# Power.net
KiCad netlist of a schematic drawn in Altium Designer
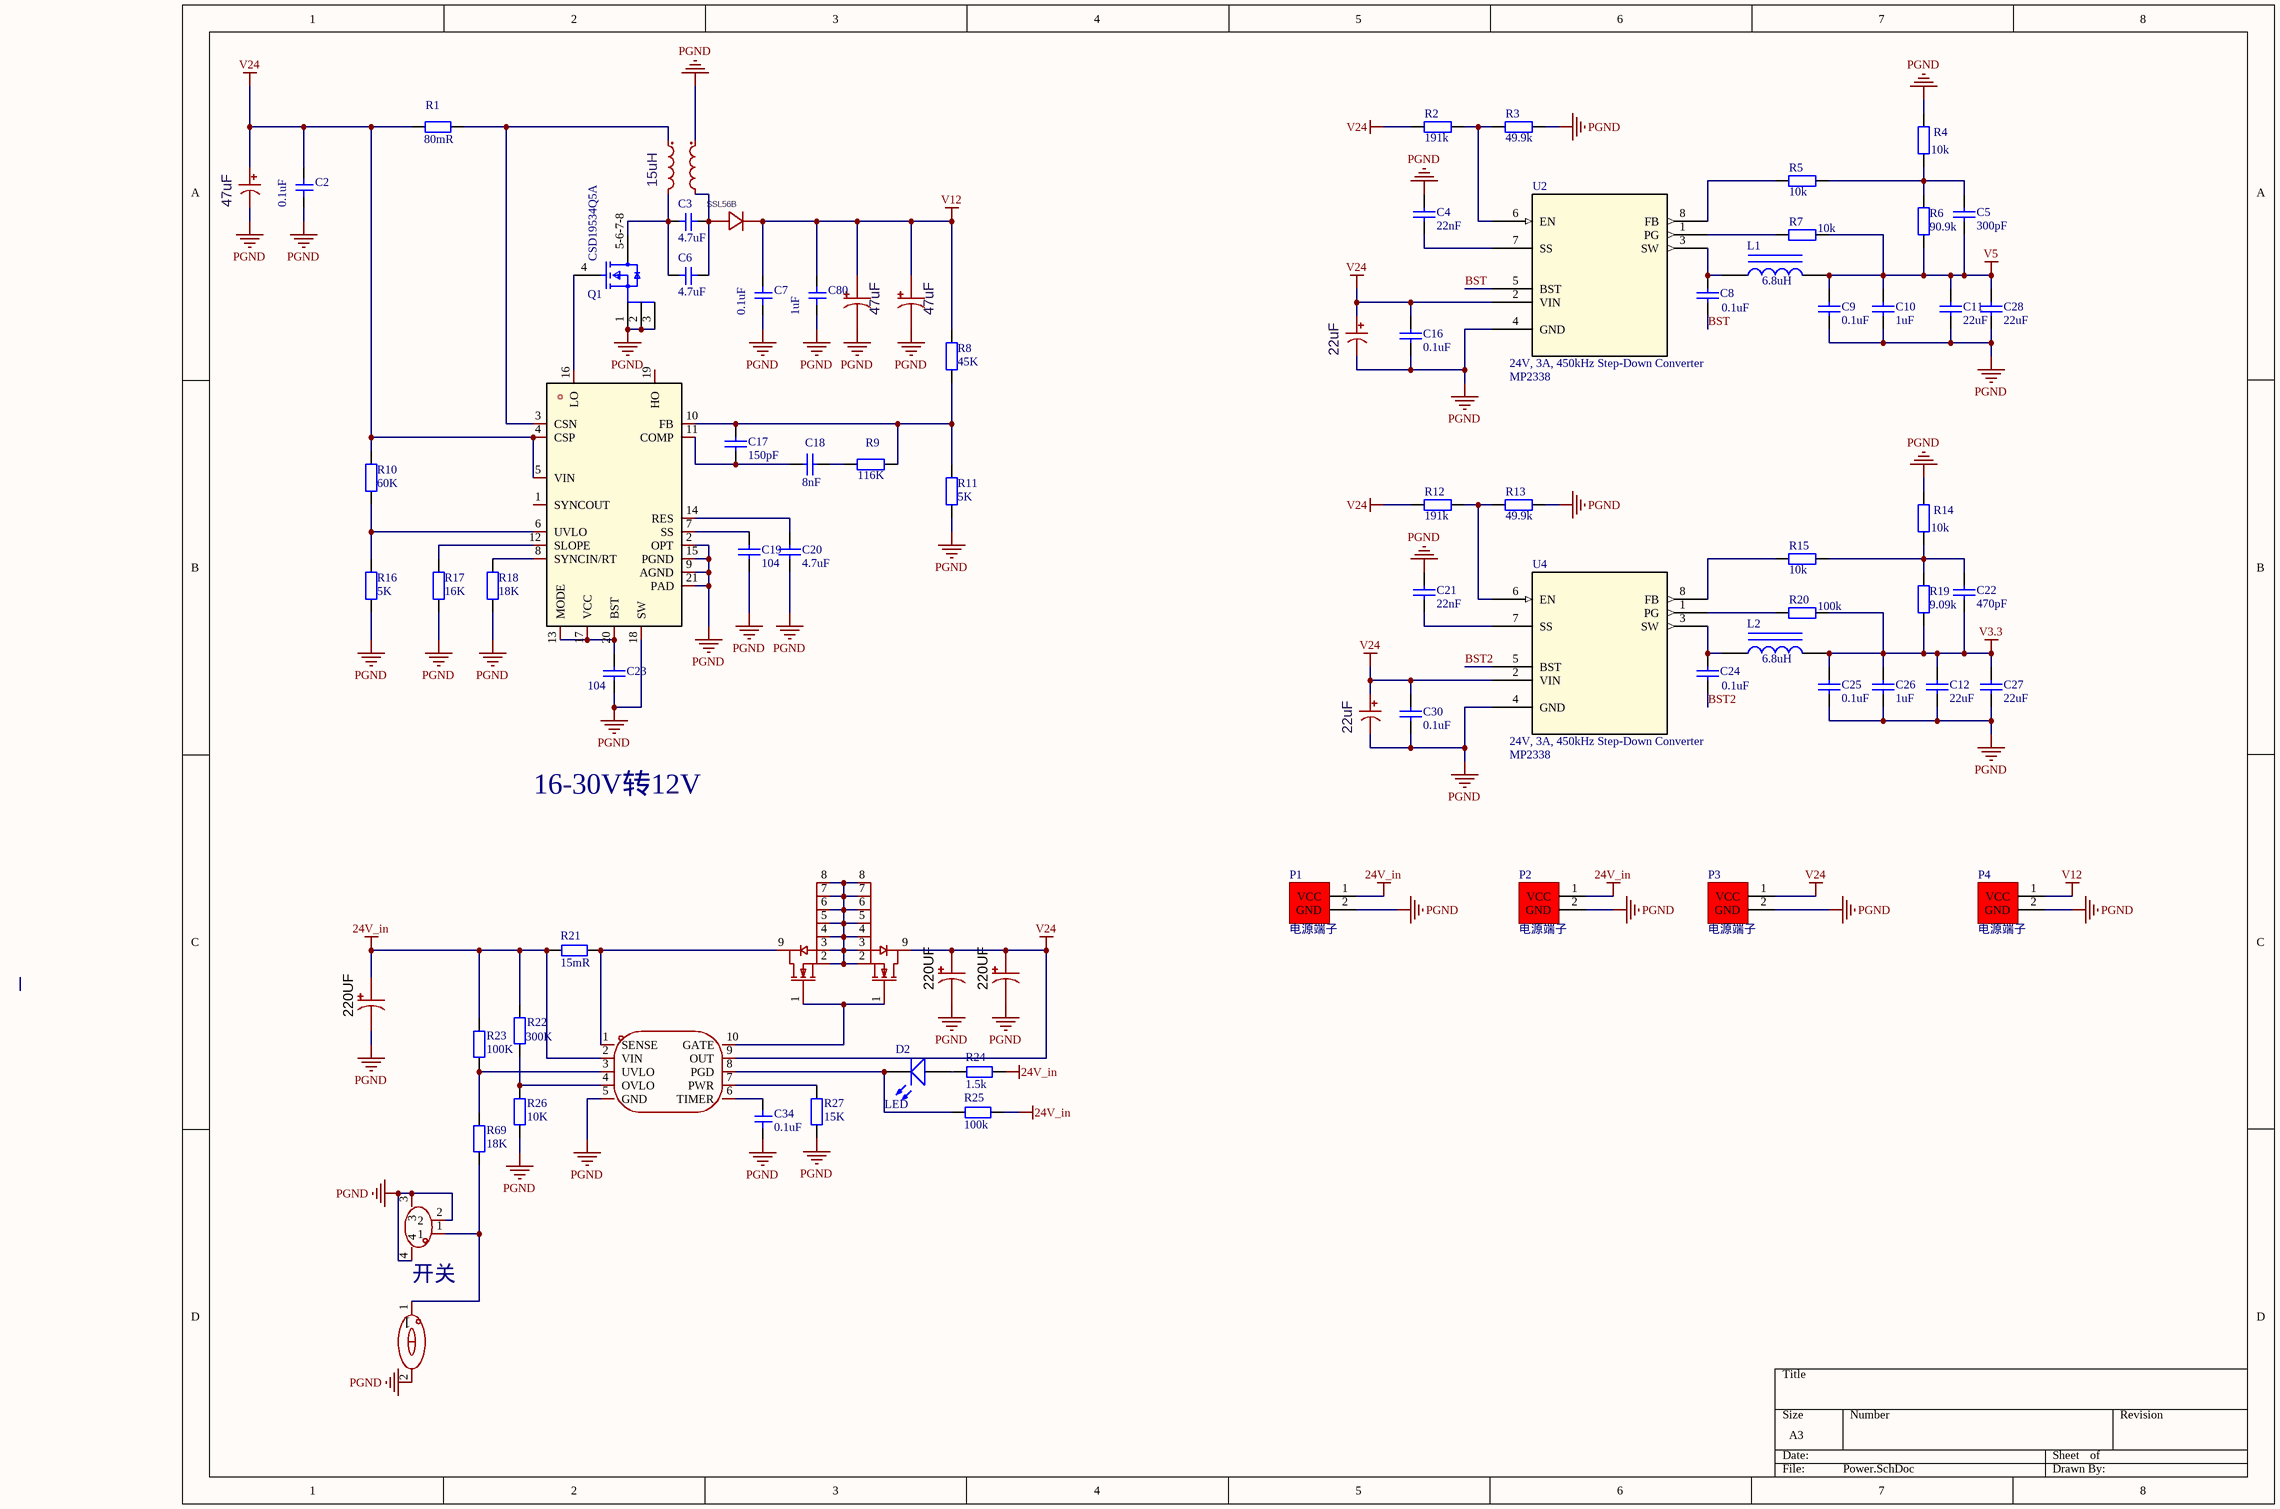
[diagram p0: Power.SchDoc]

(export (version "E")
  (design (tool "Eeschema 10.0.6"))
  (components
    (comp (ref "C1")
      (value "47uF")
      (footprint "CAP-SMD_BD6.3-L6.6-W6.6-LS7.6-FD")
      (description "电解电容")
      (fields (field (name "MANUFACTURER") "ROQANG(容强)") (field (name "MANUFACTURER PART") "RVT1H470M0607"))
      (libsource (lib "PBK11") (part "cap"))
    )
    (comp (ref "C2")
      (value "0.1uF")
      (footprint "0603C")
      (description "无极贴片电容")
      (libsource (lib "PBK11") (part "Cap1"))
    )
    (comp (ref "C3")
      (value "4.7uF")
      (footprint "1206_C")
      (description "无极贴片电容")
      (libsource (lib "PBK11") (part "Cap1"))
    )
    (comp (ref "C4")
      (value "22nF")
      (footprint "0402_C")
      (description "贴片电容")
      (libsource (lib "SFerret") (part "SMT_Cap"))
    )
    (comp (ref "C5")
      (value "300pF")
      (footprint "0402_C")
      (description "贴片电容")
      (libsource (lib "SFerret") (part "SMT_Cap"))
    )
    (comp (ref "C6")
      (value "4.7uF")
      (footprint "1206_C")
      (description "无极贴片电容")
      (libsource (lib "PBK11") (part "Cap1"))
    )
    (comp (ref "C7")
      (value "0.1uF")
      (footprint "0603C")
      (description "无极贴片电容")
      (libsource (lib "PBK11") (part "Cap1"))
    )
    (comp (ref "C8")
      (value "0.1uF")
      (footprint "0603_C")
      (description "贴片电容")
      (libsource (lib "SFerret") (part "SMT_Cap"))
    )
    (comp (ref "C9")
      (value "0.1uF")
      (footprint "0603_C")
      (description "贴片电容")
      (libsource (lib "SFerret") (part "SMT_Cap"))
    )
    (comp (ref "C10")
      (value "1uF")
      (footprint "0603_C")
      (description "贴片电容")
      (libsource (lib "SFerret") (part "SMT_Cap"))
    )
    (comp (ref "C11")
      (value "22uF")
      (footprint "1210_C")
      (description "贴片电容")
      (libsource (lib "SFerret") (part "SMT_Cap"))
    )
    (comp (ref "C12")
      (value "22uF")
      (footprint "1210_C")
      (description "贴片电容")
      (libsource (lib "SFerret") (part "SMT_Cap"))
    )
    (comp (ref "C13")
      (value "47uF")
      (footprint "CAP-SMD_BD6.3-L6.6-W6.6-LS7.6-FD")
      (description "47uf 63v 2.1A@100KHZ")
      (fields (field (name "MANUFACTURER") "PANASONIC(松下)") (field (name "MANUFACTURER PART") "50SVPF39M"))
      (libsource (lib "PBK11") (part "cap2"))
    )
    (comp (ref "C14")
      (value "47uF")
      (footprint "CAP-SMD_BD6.3-L6.6-W6.6-LS7.6-FD")
      (description "47uf 63v 2.1A@100KHZ")
      (fields (field (name "MANUFACTURER") "PANASONIC(松下)") (field (name "MANUFACTURER PART") "50SVPF39M"))
      (libsource (lib "PBK11") (part "cap2"))
    )
    (comp (ref "C15")
      (value "22uF")
      (footprint "CAP-SMD_BD6.3-L6.6-W6.6-LS7.6-FD")
      (description "电解电容")
      (fields (field (name "MANUFACTURER") "ROQANG(容强)") (field (name "MANUFACTURER PART") "RVT1H470M0607"))
      (libsource (lib "PBK11") (part "cap"))
    )
    (comp (ref "C16")
      (value "0.1uF")
      (footprint "0603_C")
      (description "贴片电容")
      (libsource (lib "SFerret") (part "SMT_Cap"))
    )
    (comp (ref "C17")
      (value "150pF")
      (footprint "0402_C")
      (description "贴片电容")
      (libsource (lib "PBK11") (part "SMT_Cap"))
    )
    (comp (ref "C18")
      (value "8nF")
      (footprint "0402_C")
      (description "贴片电容")
      (libsource (lib "PBK11") (part "SMT_Cap"))
    )
    (comp (ref "C19")
      (value "104")
      (footprint "0402_C")
      (description "贴片电容")
      (libsource (lib "PBK11") (part "SMT_Cap"))
    )
    (comp (ref "C20")
      (value "4.7uF")
      (footprint "0603_C")
      (description "贴片电容")
      (libsource (lib "PBK11") (part "SMT_Cap"))
    )
    (comp (ref "C21")
      (value "22nF")
      (footprint "0402_C")
      (description "贴片电容")
      (libsource (lib "SFerret") (part "SMT_Cap"))
    )
    (comp (ref "C22")
      (value "470pF")
      (footprint "0402_C")
      (description "贴片电容")
      (libsource (lib "SFerret") (part "SMT_Cap"))
    )
    (comp (ref "C23")
      (value "104")
      (footprint "0402_C")
      (description "贴片电容")
      (libsource (lib "PBK11") (part "SMT_Cap"))
    )
    (comp (ref "C24")
      (value "0.1uF")
      (footprint "0603_C")
      (description "贴片电容")
      (libsource (lib "SFerret") (part "SMT_Cap"))
    )
    (comp (ref "C25")
      (value "0.1uF")
      (footprint "0603_C")
      (description "贴片电容")
      (libsource (lib "SFerret") (part "SMT_Cap"))
    )
    (comp (ref "C26")
      (value "1uF")
      (footprint "0603_C")
      (description "贴片电容")
      (libsource (lib "SFerret") (part "SMT_Cap"))
    )
    (comp (ref "C27")
      (value "22uF")
      (footprint "1210_C")
      (description "贴片电容")
      (libsource (lib "SFerret") (part "SMT_Cap"))
    )
    (comp (ref "C28")
      (value "22uF")
      (footprint "1210_C")
      (description "贴片电容")
      (libsource (lib "SFerret") (part "SMT_Cap"))
    )
    (comp (ref "C29")
      (value "22uF")
      (footprint "CAP-SMD_BD6.3-L6.6-W6.6-LS7.6-FD")
      (description "电解电容")
      (fields (field (name "MANUFACTURER") "ROQANG(容强)") (field (name "MANUFACTURER PART") "RVT1H470M0607"))
      (libsource (lib "PBK11") (part "cap"))
    )
    (comp (ref "C30")
      (value "0.1uF")
      (footprint "0603_C")
      (description "贴片电容")
      (libsource (lib "SFerret") (part "SMT_Cap"))
    )
    (comp (ref "C31")
      (value "220UF")
      (footprint "CAP-SMD_BD10.0-L10.3-W10.3-LS11.3-FD")
      (description "4.7uf 50v 14mA@120HZ")
      (fields (field (name "MANUFACTURER") "ROQANG(容强)") (field (name "MANUFACTURER PART") "VT1H4R7M0405"))
      (libsource (lib "") (part "cap_1"))
    )
    (comp (ref "C32")
      (value "220UF")
      (footprint "CAP-SMD_BD10.0-L10.3-W10.3-LS11.3-FD")
      (description "4.7uf 50v 14mA@120HZ")
      (fields (field (name "MANUFACTURER") "ROQANG(容强)") (field (name "MANUFACTURER PART") "VT1H4R7M0405"))
      (libsource (lib "") (part "cap_1"))
    )
    (comp (ref "C33")
      (value "220UF")
      (footprint "CAP-SMD_BD10.0-L10.3-W10.3-LS11.3-FD")
      (description "4.7uf 50v 14mA@120HZ")
      (fields (field (name "MANUFACTURER") "ROQANG(容强)") (field (name "MANUFACTURER PART") "VT1H4R7M0405"))
      (libsource (lib "") (part "cap_1"))
    )
    (comp (ref "C34")
      (value "0.1uF")
      (footprint "0402_C")
      (description "无极贴片电容")
      (libsource (lib "PBK11") (part "Cap1"))
    )
    (comp (ref "C80")
      (value "1uF")
      (footprint "0603C")
      (description "无极贴片电容")
      (libsource (lib "PBK11") (part "Cap1"))
    )
    (comp (ref "D1")
      (value "SSL56B")
      (footprint "SMBF_L4.3-W3.6-LS5.3-RD")
      (description "正向压降(Vf): 500mV@5A\r\n直流反向耐压(Vr): 60V\r\n整流电流: 5A 肖特基二极管")
      (fields (field (name "MANUFACTURER") "宏迦橙"))
      (libsource (lib "PBK11") (part "SSL56B_C28646279"))
    )
    (comp (ref "D2")
      (value "LED")
      (footprint "0805_LED")
      (description "发光二极管")
      (libsource (lib "PBK11") (part "LED"))
    )
    (comp (ref "L1")
      (value "6.8uH")
      (footprint "IND-SMD_L7.0-W6.6")
      (description "功率电感")
      (libsource (lib "SFerret") (part "SMT_Iud_Power"))
    )
    (comp (ref "L2")
      (value "6.8uH")
      (footprint "IND-SMD_L7.0-W6.6")
      (description "功率电感")
      (libsource (lib "SFerret") (part "SMT_Iud_Power"))
    )
    (comp (ref "P1") (value "电源端子") (footprint "XT60PB-F") (libsource (lib "PBK11") (part "电源端子")))
    (comp (ref "P2") (value "电源端子") (footprint "XT60PB-F") (libsource (lib "PBK11") (part "电源端子")))
    (comp (ref "P3") (value "电源端子") (footprint "XT60PB-F") (libsource (lib "PBK11") (part "电源端子")))
    (comp (ref "P4") (value "电源端子") (footprint "XT30-F") (libsource (lib "PBK11") (part "电源端子")))
    (comp (ref "Q1")
      (value "CSD19534Q5A")
      (footprint "FP-DQJ0008A-MFG")
      (description "MOSFET N-CH 100V 50 8SON")
      (fields
        (field (name "OCTOPART") "https://octopart.com/csd19534q5a-texas+instruments-46749514")
        (field (name "MANUFACTURER") "Texas Instruments")
      )
      (libsource (lib "PBK11") (part "CMP-04962-000018-1"))
    )
    (comp (ref "Q2")
      (value "HYG006N04LS1TA")
      (footprint "TOLL-8_L10.4-W9.9-P1.20-LS11.7-BL")
      (fields (field (name "MANUFACTURER") "HUAYI(华羿微)"))
      (libsource (lib "PBK11") (part "HYG006N04LS1TA"))
    )
    (comp (ref "Q3")
      (value "HYG006N04LS1TA")
      (footprint "TOLL-8_L10.4-W9.9-P1.20-LS11.7-BL")
      (fields (field (name "MANUFACTURER") "HUAYI(华羿微)"))
      (libsource (lib "PBK11") (part "HYG006N04LS1TA"))
    )
    (comp (ref "R1")
      (value "80mR")
      (footprint "2512")
      (description "电阻")
      (libsource (lib "PBK11") (part "Res"))
    )
    (comp (ref "R2")
      (value "191k")
      (footprint "0402_R")
      (description "贴片电阻")
      (libsource (lib "SFerret") (part "SMT_Res"))
    )
    (comp (ref "R3")
      (value "49.9k")
      (footprint "0402_R")
      (description "贴片电阻")
      (libsource (lib "SFerret") (part "SMT_Res"))
    )
    (comp (ref "R4")
      (value "10k")
      (footprint "0402_R")
      (description "贴片电阻")
      (libsource (lib "") (part "SMT_Res_1"))
    )
    (comp (ref "R5")
      (value "10k")
      (footprint "0402_R")
      (description "贴片电阻")
      (libsource (lib "SFerret") (part "SMT_Res"))
    )
    (comp (ref "R6")
      (value "90.9k")
      (footprint "0402_R")
      (description "贴片电阻")
      (libsource (lib "") (part "SMT_Res_1"))
    )
    (comp (ref "R7")
      (value "10k")
      (footprint "0402_R")
      (description "贴片电阻")
      (libsource (lib "") (part "SMT_Res_2"))
    )
    (comp (ref "R8")
      (value "45K")
      (footprint "0402_R")
      (description "贴片电阻")
      (libsource (lib "") (part "SMT_Res_1"))
    )
    (comp (ref "R9")
      (value "116K")
      (footprint "0402_R")
      (description "贴片电阻")
      (libsource (lib "PBK11") (part "SMT_Res"))
    )
    (comp (ref "R10")
      (value "60K")
      (footprint "0402_R")
      (description "贴片电阻")
      (libsource (lib "PBK11") (part "SMT_Res_1"))
    )
    (comp (ref "R11")
      (value "5K")
      (footprint "0402_R")
      (description "贴片电阻")
      (libsource (lib "") (part "SMT_Res_1"))
    )
    (comp (ref "R12")
      (value "191k")
      (footprint "0402_R")
      (description "贴片电阻")
      (libsource (lib "SFerret") (part "SMT_Res"))
    )
    (comp (ref "R13")
      (value "49.9k")
      (footprint "0402_R")
      (description "贴片电阻")
      (libsource (lib "SFerret") (part "SMT_Res"))
    )
    (comp (ref "R14")
      (value "10k")
      (footprint "0402_R")
      (description "贴片电阻")
      (libsource (lib "") (part "SMT_Res_1"))
    )
    (comp (ref "R15")
      (value "10k")
      (footprint "0402_R")
      (description "贴片电阻")
      (libsource (lib "SFerret") (part "SMT_Res"))
    )
    (comp (ref "R16")
      (value "5K")
      (footprint "0402_R")
      (description "贴片电阻")
      (libsource (lib "PBK11") (part "SMT_Res_1"))
    )
    (comp (ref "R17")
      (value "16K")
      (footprint "0402_R")
      (description "贴片电阻")
      (libsource (lib "PBK11") (part "SMT_Res_1"))
    )
    (comp (ref "R18")
      (value "18K")
      (footprint "0402_R")
      (description "贴片电阻")
      (libsource (lib "PBK11") (part "SMT_Res_1"))
    )
    (comp (ref "R19")
      (value "9.09k")
      (footprint "0402_R")
      (description "贴片电阻")
      (libsource (lib "") (part "SMT_Res_1"))
    )
    (comp (ref "R20")
      (value "100k")
      (footprint "0402_R")
      (description "贴片电阻")
      (libsource (lib "") (part "SMT_Res_2"))
    )
    (comp (ref "R21")
      (value "15mR")
      (footprint "2512")
      (description "电阻")
      (libsource (lib "PBK11") (part "Res"))
    )
    (comp (ref "R22")
      (value "300K")
      (footprint "0402_R")
      (description "电阻")
      (libsource (lib "PBK11") (part "Res"))
    )
    (comp (ref "R23")
      (value "100K")
      (footprint "0402_R")
      (description "电阻")
      (libsource (lib "PBK11") (part "Res"))
    )
    (comp (ref "R24")
      (value "1.5k")
      (footprint "0402_R")
      (description "电阻")
      (libsource (lib "PBK11") (part "Res"))
    )
    (comp (ref "R25")
      (value "100k")
      (footprint "0402_R")
      (description "电阻")
      (libsource (lib "PBK11") (part "Res"))
    )
    (comp (ref "R26")
      (value "10K")
      (footprint "0402_R")
      (description "电阻")
      (libsource (lib "PBK11") (part "Res"))
    )
    (comp (ref "R27")
      (value "15K")
      (footprint "0402_R")
      (description "电阻")
      (libsource (lib "PBK11") (part "Res"))
    )
    (comp (ref "R69")
      (value "18K")
      (footprint "0402_R")
      (description "电阻")
      (libsource (lib "PBK11") (part "Res"))
    )
    (comp (ref "SW1")
      (value "DSIC01LS-P")
      (footprint "SW-SMD_2P-L3.5-W6.2-P2.54-LS9.8")
      (description "1P")
      (fields (field (name "MANUFACTURER") "XKB Connectivity(中国星坤)"))
      (libsource (lib "PBK11") (part "拨码开关"))
    )
    (comp (ref "U1")
      (value "15uH")
      (footprint "IND-SMD_4P-L12.0-W12.0_496R8C")
      (description "耦合电感 15uH 5A")
      (fields
        (field (name "MANUFACTURER") "YJYCOIN(益嘉源)")
        (field (name "MANUFACTURER PART") "YPRH1207C-150M")
      )
      (libsource (lib "PBK11") (part "YPRH1207C-150M"))
    )
    (comp (ref "U2")
      (value "24V, 3A, 450kHz Step-Down Converter")
      (footprint "SOT583_MP2338_MNP")
      (description "High-Efficiency, 28V, 3A, 450kHz,\r\nSynchronous Step-Down Converter\r\nIn SOT583 Package")
      (libsource (lib "SFerret") (part "MP2338GTL-P"))
    )
    (comp (ref "U3")
      (value "LM5122MHX/NOPB")
      (footprint "HTSSOP-20_L6.5-W4.4-P0.65-LS6.4-BL-EP")
      (fields (field (name "MANUFACTURER") "TI(德州仪器)"))
      (libsource (lib "PBK11") (part "LM5122MHX/NOPB"))
    )
    (comp (ref "U4")
      (value "24V, 3A, 450kHz Step-Down Converter")
      (footprint "SOT583_MP2338_MNP")
      (description "High-Efficiency, 28V, 3A, 450kHz,\r\nSynchronous Step-Down Converter\r\nIn SOT583 Package")
      (libsource (lib "SFerret") (part "MP2338GTL-P"))
    )
    (comp (ref "U5")
      (value "LM5069MMX-2/NOPB")
      (footprint "VSSOP-10_L3.0-W3.0-P0.50-LS4.9-BL")
      (fields (field (name "MANUFACTURER") "TI(德州仪器)"))
      (libsource (lib "PBK11") (part "LM5069MMX-2/NOPB"))
    )
    (comp (ref "U6")
      (value "ZX-XH2.54-2PLT")
      (footprint "HC-1.25-2")
      (fields (field (name "MANUFACTURER") "Megastar(兆星)"))
      (libsource (lib "PBK11") (part "ZX-XH2.54-2PLT"))
    )
  )
  (nets
    (net (code "1") (name "/BST") (class "Default")
      (node (ref "C8") (pin "1") (pinfunction "1_1") (pintype "passive"))
      (node (ref "U2") (pin "5") (pinfunction "BST_5") (pintype "power_in"))
    )
    (net (code "2") (name "/BST2") (class "Default")
      (node (ref "C24") (pin "1") (pinfunction "1_1") (pintype "passive"))
      (node (ref "U4") (pin "5") (pinfunction "BST_5") (pintype "power_in"))
    )
    (net (code "3") (name "24V_in") (class "Default")
      (node (ref "C33") (pin "1") (pinfunction "1_1") (pintype "passive"))
      (node (ref "P1") (pin "1") (pinfunction "VCC_1") (pintype "passive"))
      (node (ref "P2") (pin "1") (pinfunction "VCC_1") (pintype "passive"))
      (node (ref "R21") (pin "2") (pinfunction "2_2") (pintype "passive"))
      (node (ref "R22") (pin "2") (pinfunction "2_2") (pintype "passive"))
      (node (ref "R23") (pin "2") (pinfunction "2_2") (pintype "passive"))
      (node (ref "R24") (pin "1") (pinfunction "1_1") (pintype "passive"))
      (node (ref "R25") (pin "1") (pinfunction "1_1") (pintype "passive"))
      (node (ref "U5") (pin "2") (pinfunction "VIN_2") (pintype "passive"))
    )
    (net (code "4") (name "Net-(C3-Pad2)") (class "Default")
      (node (ref "C3") (pin "2") (pinfunction "2_2") (pintype "passive"))
      (node (ref "C6") (pin "2") (pinfunction "2_2") (pintype "passive"))
      (node (ref "D1") (pin "2") (pinfunction "2_2") (pintype "passive"))
      (node (ref "U1") (pin "4") (pinfunction "4_4") (pintype "passive"))
    )
    (net (code "5") (name "Net-(C5-Pad2)") (class "Default")
      (node (ref "C5") (pin "2") (pinfunction "2_2") (pintype "passive"))
      (node (ref "R4") (pin "1") (pinfunction "1_1") (pintype "passive"))
      (node (ref "R5") (pin "1") (pinfunction "1_1") (pintype "passive"))
      (node (ref "R6") (pin "2") (pinfunction "2_2") (pintype "passive"))
    )
    (net (code "6") (name "Net-(C18-Pad2)") (class "Default")
      (node (ref "C18") (pin "2") (pinfunction "2_2") (pintype "passive"))
      (node (ref "R9") (pin "1") (pinfunction "1_1") (pintype "passive"))
    )
    (net (code "7") (name "Net-(C22-Pad2)") (class "Default")
      (node (ref "C22") (pin "2") (pinfunction "2_2") (pintype "passive"))
      (node (ref "R14") (pin "1") (pinfunction "1_1") (pintype "passive"))
      (node (ref "R15") (pin "1") (pinfunction "1_1") (pintype "passive"))
      (node (ref "R19") (pin "2") (pinfunction "2_2") (pintype "passive"))
    )
    (net (code "8") (name "Net-(D2-PadA)") (class "Default")
      (node (ref "D2") (pin "A") (pinfunction "A_A") (pintype "passive"))
      (node (ref "R24") (pin "2") (pinfunction "2_2") (pintype "passive"))
    )
    (net (code "9") (name "Net-(Q1-D)") (class "Default")
      (node (ref "C3") (pin "1") (pinfunction "1_1") (pintype "passive"))
      (node (ref "C6") (pin "1") (pinfunction "1_1") (pintype "passive"))
      (node (ref "Q1") (pin "5-6-7-8") (pinfunction "D_5-6-7-8") (pintype "passive"))
      (node (ref "U1") (pin "3") (pinfunction "3_3") (pintype "passive"))
    )
    (net (code "10") (name "Net-(Q1-G)") (class "Default")
      (node (ref "Q1") (pin "4") (pinfunction "G_4") (pintype "passive"))
      (node (ref "U3") (pin "16") (pinfunction "LO_16") (pintype "passive"))
    )
    (net (code "11") (name "Net-(Q2-D)") (class "Default")
      (node (ref "Q2") (pin "9") (pinfunction "D_9") (pintype "passive"))
      (node (ref "R21") (pin "1") (pinfunction "1_1") (pintype "passive"))
      (node (ref "U5") (pin "1") (pinfunction "SENSE_1") (pintype "passive"))
    )
    (net (code "12") (name "Net-(Q2-G)") (class "Default")
      (node (ref "Q2") (pin "1") (pinfunction "G_1") (pintype "passive"))
      (node (ref "Q3") (pin "1") (pinfunction "G_1") (pintype "passive"))
      (node (ref "U5") (pin "10") (pinfunction "GATE_10") (pintype "passive"))
    )
    (net (code "13") (name "Net-(Q2-S-Pad2)") (class "Default")
      (node (ref "Q2") (pin "2") (pinfunction "S_2") (pintype "passive"))
      (node (ref "Q2") (pin "3") (pinfunction "S_3") (pintype "passive"))
      (node (ref "Q2") (pin "4") (pinfunction "S_4") (pintype "passive"))
      (node (ref "Q2") (pin "5") (pinfunction "S_5") (pintype "passive"))
      (node (ref "Q2") (pin "6") (pinfunction "S_6") (pintype "passive"))
      (node (ref "Q2") (pin "7") (pinfunction "S_7") (pintype "passive"))
      (node (ref "Q2") (pin "8") (pinfunction "S_8") (pintype "passive"))
      (node (ref "Q3") (pin "2") (pinfunction "S_2") (pintype "passive"))
      (node (ref "Q3") (pin "3") (pinfunction "S_3") (pintype "passive"))
      (node (ref "Q3") (pin "4") (pinfunction "S_4") (pintype "passive"))
      (node (ref "Q3") (pin "5") (pinfunction "S_5") (pintype "passive"))
      (node (ref "Q3") (pin "6") (pinfunction "S_6") (pintype "passive"))
      (node (ref "Q3") (pin "7") (pinfunction "S_7") (pintype "passive"))
      (node (ref "Q3") (pin "8") (pinfunction "S_8") (pintype "passive"))
    )
    (net (code "14") (name "Net-(SW1-PIN1)") (class "Default")
      (node (ref "R69") (pin "1") (pinfunction "1_1") (pintype "passive"))
      (node (ref "SW1") (pin "1") (pinfunction "PIN1_1") (pintype "passive"))
      (node (ref "U6") (pin "1") (pinfunction "1_1") (pintype "passive"))
    )
    (net (code "15") (name "Net-(U2-EN)") (class "Default")
      (node (ref "R2") (pin "1") (pinfunction "1_1") (pintype "passive"))
      (node (ref "R3") (pin "2") (pinfunction "2_2") (pintype "passive"))
      (node (ref "U2") (pin "6") (pinfunction "EN_6") (pintype "input"))
    )
    (net (code "16") (name "Net-(U2-FB)") (class "Default")
      (node (ref "R5") (pin "2") (pinfunction "2_2") (pintype "passive"))
      (node (ref "U2") (pin "8") (pinfunction "FB_8") (pintype "output"))
    )
    (net (code "17") (name "Net-(U2-PG)") (class "Default")
      (node (ref "R7") (pin "1") (pinfunction "1_1") (pintype "passive"))
      (node (ref "U2") (pin "1") (pinfunction "PG_1") (pintype "output"))
    )
    (net (code "18") (name "Net-(U2-SS)") (class "Default")
      (node (ref "C4") (pin "1") (pinfunction "1_1") (pintype "passive"))
      (node (ref "U2") (pin "7") (pinfunction "SS_7") (pintype "passive"))
    )
    (net (code "19") (name "Net-(U2-SW)") (class "Default")
      (node (ref "C8") (pin "2") (pinfunction "2_2") (pintype "passive"))
      (node (ref "L1") (pin "1") (pinfunction "1_1") (pintype "passive"))
      (node (ref "U2") (pin "3") (pinfunction "SW_3") (pintype "output"))
    )
    (net (code "20") (name "Net-(U3-BST)") (class "Default")
      (node (ref "C23") (pin "2") (pinfunction "2_2") (pintype "passive"))
      (node (ref "U3") (pin "13") (pinfunction "MODE_13") (pintype "passive"))
      (node (ref "U3") (pin "17") (pinfunction "VCC_17") (pintype "passive"))
      (node (ref "U3") (pin "20") (pinfunction "BST_20") (pintype "passive"))
    )
    (net (code "21") (name "Net-(U3-COMP)") (class "Default")
      (node (ref "C17") (pin "1") (pinfunction "1_1") (pintype "passive"))
      (node (ref "C18") (pin "1") (pinfunction "1_1") (pintype "passive"))
      (node (ref "U3") (pin "11") (pinfunction "COMP_11") (pintype "passive"))
    )
    (net (code "22") (name "Net-(U3-CSN)") (class "Default")
      (node (ref "R1") (pin "2") (pinfunction "2_2") (pintype "passive"))
      (node (ref "U1") (pin "1") (pinfunction "1_1") (pintype "passive"))
      (node (ref "U3") (pin "3") (pinfunction "CSN_3") (pintype "passive"))
    )
    (net (code "23") (name "Net-(U3-FB)") (class "Default")
      (node (ref "C17") (pin "2") (pinfunction "2_2") (pintype "passive"))
      (node (ref "R11") (pin "2") (pinfunction "2_2") (pintype "passive"))
      (node (ref "R8") (pin "1") (pinfunction "1_1") (pintype "passive"))
      (node (ref "R9") (pin "2") (pinfunction "2_2") (pintype "passive"))
      (node (ref "U3") (pin "10") (pinfunction "FB_10") (pintype "passive"))
    )
    (net (code "24") (name "Net-(U3-RES)") (class "Default")
      (node (ref "C20") (pin "2") (pinfunction "2_2") (pintype "passive"))
      (node (ref "U3") (pin "14") (pinfunction "RES_14") (pintype "passive"))
    )
    (net (code "25") (name "Net-(U3-SLOPE)") (class "Default")
      (node (ref "R17") (pin "2") (pinfunction "2_2") (pintype "passive"))
      (node (ref "U3") (pin "12") (pinfunction "SLOPE_12") (pintype "passive"))
    )
    (net (code "26") (name "Net-(U3-SS)") (class "Default")
      (node (ref "C19") (pin "2") (pinfunction "2_2") (pintype "passive"))
      (node (ref "U3") (pin "7") (pinfunction "SS_7") (pintype "passive"))
    )
    (net (code "27") (name "Net-(U3-SYNCIN{slash}RT)") (class "Default")
      (node (ref "R18") (pin "2") (pinfunction "2_2") (pintype "passive"))
      (node (ref "U3") (pin "8") (pinfunction "SYNCIN/RT_8") (pintype "passive"))
    )
    (net (code "28") (name "Net-(U3-UVLO)") (class "Default")
      (node (ref "R10") (pin "1") (pinfunction "1_1") (pintype "passive"))
      (node (ref "R16") (pin "2") (pinfunction "2_2") (pintype "passive"))
      (node (ref "U3") (pin "6") (pinfunction "UVLO_6") (pintype "passive"))
    )
    (net (code "29") (name "Net-(U4-EN)") (class "Default")
      (node (ref "R12") (pin "1") (pinfunction "1_1") (pintype "passive"))
      (node (ref "R13") (pin "2") (pinfunction "2_2") (pintype "passive"))
      (node (ref "U4") (pin "6") (pinfunction "EN_6") (pintype "input"))
    )
    (net (code "30") (name "Net-(U4-FB)") (class "Default")
      (node (ref "R15") (pin "2") (pinfunction "2_2") (pintype "passive"))
      (node (ref "U4") (pin "8") (pinfunction "FB_8") (pintype "output"))
    )
    (net (code "31") (name "Net-(U4-PG)") (class "Default")
      (node (ref "R20") (pin "1") (pinfunction "1_1") (pintype "passive"))
      (node (ref "U4") (pin "1") (pinfunction "PG_1") (pintype "output"))
    )
    (net (code "32") (name "Net-(U4-SS)") (class "Default")
      (node (ref "C21") (pin "1") (pinfunction "1_1") (pintype "passive"))
      (node (ref "U4") (pin "7") (pinfunction "SS_7") (pintype "passive"))
    )
    (net (code "33") (name "Net-(U4-SW)") (class "Default")
      (node (ref "C24") (pin "2") (pinfunction "2_2") (pintype "passive"))
      (node (ref "L2") (pin "1") (pinfunction "1_1") (pintype "passive"))
      (node (ref "U4") (pin "3") (pinfunction "SW_3") (pintype "output"))
    )
    (net (code "34") (name "Net-(U5-OVLO)") (class "Default")
      (node (ref "R22") (pin "1") (pinfunction "1_1") (pintype "passive"))
      (node (ref "R26") (pin "2") (pinfunction "2_2") (pintype "passive"))
      (node (ref "U5") (pin "4") (pinfunction "OVLO_4") (pintype "passive"))
    )
    (net (code "35") (name "Net-(U5-PGD)") (class "Default")
      (node (ref "D2") (pin "K") (pinfunction "K_K") (pintype "passive"))
      (node (ref "R25") (pin "2") (pinfunction "2_2") (pintype "passive"))
      (node (ref "U5") (pin "8") (pinfunction "PGD_8") (pintype "passive"))
    )
    (net (code "36") (name "Net-(U5-PWR)") (class "Default")
      (node (ref "R27") (pin "1") (pinfunction "1_1") (pintype "passive"))
      (node (ref "U5") (pin "7") (pinfunction "PWR_7") (pintype "passive"))
    )
    (net (code "37") (name "Net-(U5-TIMER)") (class "Default")
      (node (ref "C34") (pin "2") (pinfunction "2_2") (pintype "passive"))
      (node (ref "U5") (pin "6") (pinfunction "TIMER_6") (pintype "passive"))
    )
    (net (code "38") (name "Net-(U5-UVLO)") (class "Default")
      (node (ref "R23") (pin "1") (pinfunction "1_1") (pintype "passive"))
      (node (ref "R69") (pin "2") (pinfunction "2_2") (pintype "passive"))
      (node (ref "U5") (pin "3") (pinfunction "UVLO_3") (pintype "passive"))
    )
    (net (code "39") (name "PGND") (class "Default")
      (node (ref "C1") (pin "2") (pinfunction "2_2") (pintype "passive"))
      (node (ref "C10") (pin "1") (pinfunction "1_1") (pintype "passive"))
      (node (ref "C11") (pin "1") (pinfunction "1_1") (pintype "passive"))
      (node (ref "C12") (pin "1") (pinfunction "1_1") (pintype "passive"))
      (node (ref "C13") (pin "2") (pinfunction "2_2") (pintype "passive"))
      (node (ref "C14") (pin "2") (pinfunction "2_2") (pintype "passive"))
      (node (ref "C15") (pin "2") (pinfunction "2_2") (pintype "passive"))
      (node (ref "C16") (pin "1") (pinfunction "1_1") (pintype "passive"))
      (node (ref "C19") (pin "1") (pinfunction "1_1") (pintype "passive"))
      (node (ref "C2") (pin "1") (pinfunction "1_1") (pintype "passive"))
      (node (ref "C20") (pin "1") (pinfunction "1_1") (pintype "passive"))
      (node (ref "C21") (pin "2") (pinfunction "2_2") (pintype "passive"))
      (node (ref "C23") (pin "1") (pinfunction "1_1") (pintype "passive"))
      (node (ref "C25") (pin "1") (pinfunction "1_1") (pintype "passive"))
      (node (ref "C26") (pin "1") (pinfunction "1_1") (pintype "passive"))
      (node (ref "C27") (pin "1") (pinfunction "1_1") (pintype "passive"))
      (node (ref "C28") (pin "1") (pinfunction "1_1") (pintype "passive"))
      (node (ref "C29") (pin "2") (pinfunction "2_2") (pintype "passive"))
      (node (ref "C30") (pin "1") (pinfunction "1_1") (pintype "passive"))
      (node (ref "C31") (pin "2") (pinfunction "2_2") (pintype "passive"))
      (node (ref "C32") (pin "2") (pinfunction "2_2") (pintype "passive"))
      (node (ref "C33") (pin "2") (pinfunction "2_2") (pintype "passive"))
      (node (ref "C34") (pin "1") (pinfunction "1_1") (pintype "passive"))
      (node (ref "C4") (pin "2") (pinfunction "2_2") (pintype "passive"))
      (node (ref "C7") (pin "1") (pinfunction "1_1") (pintype "passive"))
      (node (ref "C80") (pin "1") (pinfunction "1_1") (pintype "passive"))
      (node (ref "C9") (pin "1") (pinfunction "1_1") (pintype "passive"))
      (node (ref "P1") (pin "2") (pinfunction "GND_2") (pintype "passive"))
      (node (ref "P2") (pin "2") (pinfunction "GND_2") (pintype "passive"))
      (node (ref "P3") (pin "2") (pinfunction "GND_2") (pintype "passive"))
      (node (ref "P4") (pin "2") (pinfunction "GND_2") (pintype "passive"))
      (node (ref "Q1") (pin "1") (pinfunction "S_1") (pintype "passive"))
      (node (ref "Q1") (pin "2") (pinfunction "S_2") (pintype "passive"))
      (node (ref "Q1") (pin "3") (pinfunction "S_3") (pintype "passive"))
      (node (ref "R11") (pin "1") (pinfunction "1_1") (pintype "passive"))
      (node (ref "R13") (pin "1") (pinfunction "1_1") (pintype "passive"))
      (node (ref "R14") (pin "2") (pinfunction "2_2") (pintype "passive"))
      (node (ref "R16") (pin "1") (pinfunction "1_1") (pintype "passive"))
      (node (ref "R17") (pin "1") (pinfunction "1_1") (pintype "passive"))
      (node (ref "R18") (pin "1") (pinfunction "1_1") (pintype "passive"))
      (node (ref "R26") (pin "1") (pinfunction "1_1") (pintype "passive"))
      (node (ref "R27") (pin "2") (pinfunction "2_2") (pintype "passive"))
      (node (ref "R3") (pin "1") (pinfunction "1_1") (pintype "passive"))
      (node (ref "R4") (pin "2") (pinfunction "2_2") (pintype "passive"))
      (node (ref "SW1") (pin "2") (pinfunction "PIN2_2") (pintype "passive"))
      (node (ref "U1") (pin "2") (pinfunction "2_2") (pintype "passive"))
      (node (ref "U2") (pin "4") (pinfunction "GND_4") (pintype "power_in"))
      (node (ref "U3") (pin "15") (pinfunction "PGND_15") (pintype "passive"))
      (node (ref "U3") (pin "18") (pinfunction "SW_18") (pintype "passive"))
      (node (ref "U3") (pin "2") (pinfunction "OPT_2") (pintype "passive"))
      (node (ref "U3") (pin "21") (pinfunction "PAD_21") (pintype "passive"))
      (node (ref "U3") (pin "9") (pinfunction "AGND_9") (pintype "passive"))
      (node (ref "U4") (pin "4") (pinfunction "GND_4") (pintype "power_in"))
      (node (ref "U5") (pin "5") (pinfunction "GND_5") (pintype "passive"))
      (node (ref "U6") (pin "2") (pinfunction "2_2") (pintype "passive"))
      (node (ref "U6") (pin "3") (pinfunction "3_3") (pintype "passive"))
      (node (ref "U6") (pin "4") (pinfunction "4_4") (pintype "passive"))
    )
    (net (code "40") (name "V3.3") (class "Default")
      (node (ref "C12") (pin "2") (pinfunction "2_2") (pintype "passive"))
      (node (ref "C22") (pin "1") (pinfunction "1_1") (pintype "passive"))
      (node (ref "C25") (pin "2") (pinfunction "2_2") (pintype "passive"))
      (node (ref "C26") (pin "2") (pinfunction "2_2") (pintype "passive"))
      (node (ref "C27") (pin "2") (pinfunction "2_2") (pintype "passive"))
      (node (ref "L2") (pin "2") (pinfunction "2_2") (pintype "passive"))
      (node (ref "R19") (pin "1") (pinfunction "1_1") (pintype "passive"))
      (node (ref "R20") (pin "2") (pinfunction "2_2") (pintype "passive"))
    )
    (net (code "41") (name "V5") (class "Default")
      (node (ref "C10") (pin "2") (pinfunction "2_2") (pintype "passive"))
      (node (ref "C11") (pin "2") (pinfunction "2_2") (pintype "passive"))
      (node (ref "C28") (pin "2") (pinfunction "2_2") (pintype "passive"))
      (node (ref "C5") (pin "1") (pinfunction "1_1") (pintype "passive"))
      (node (ref "C9") (pin "2") (pinfunction "2_2") (pintype "passive"))
      (node (ref "L1") (pin "2") (pinfunction "2_2") (pintype "passive"))
      (node (ref "R6") (pin "1") (pinfunction "1_1") (pintype "passive"))
      (node (ref "R7") (pin "2") (pinfunction "2_2") (pintype "passive"))
    )
    (net (code "42") (name "V12") (class "Default")
      (node (ref "C13") (pin "1") (pinfunction "1_1") (pintype "passive"))
      (node (ref "C14") (pin "1") (pinfunction "1_1") (pintype "passive"))
      (node (ref "C7") (pin "2") (pinfunction "2_2") (pintype "passive"))
      (node (ref "C80") (pin "2") (pinfunction "2_2") (pintype "passive"))
      (node (ref "D1") (pin "1") (pinfunction "1_1") (pintype "passive"))
      (node (ref "P4") (pin "1") (pinfunction "VCC_1") (pintype "passive"))
      (node (ref "R8") (pin "2") (pinfunction "2_2") (pintype "passive"))
    )
    (net (code "43") (name "V24") (class "Default")
      (node (ref "C1") (pin "1") (pinfunction "1_1") (pintype "passive"))
      (node (ref "C15") (pin "1") (pinfunction "1_1") (pintype "passive"))
      (node (ref "C16") (pin "2") (pinfunction "2_2") (pintype "passive"))
      (node (ref "C2") (pin "2") (pinfunction "2_2") (pintype "passive"))
      (node (ref "C29") (pin "1") (pinfunction "1_1") (pintype "passive"))
      (node (ref "C30") (pin "2") (pinfunction "2_2") (pintype "passive"))
      (node (ref "C31") (pin "1") (pinfunction "1_1") (pintype "passive"))
      (node (ref "C32") (pin "1") (pinfunction "1_1") (pintype "passive"))
      (node (ref "P3") (pin "1") (pinfunction "VCC_1") (pintype "passive"))
      (node (ref "Q3") (pin "9") (pinfunction "D_9") (pintype "passive"))
      (node (ref "R1") (pin "1") (pinfunction "1_1") (pintype "passive"))
      (node (ref "R10") (pin "2") (pinfunction "2_2") (pintype "passive"))
      (node (ref "R12") (pin "2") (pinfunction "2_2") (pintype "passive"))
      (node (ref "R2") (pin "2") (pinfunction "2_2") (pintype "passive"))
      (node (ref "U2") (pin "2") (pinfunction "VIN_2") (pintype "power_in"))
      (node (ref "U3") (pin "4") (pinfunction "CSP_4") (pintype "passive"))
      (node (ref "U3") (pin "5") (pinfunction "VIN_5") (pintype "passive"))
      (node (ref "U4") (pin "2") (pinfunction "VIN_2") (pintype "power_in"))
      (node (ref "U5") (pin "9") (pinfunction "OUT_9") (pintype "passive"))
    )
    (net (code "44") (name "unconnected-(U3-HO-Pad19)") (class "Default")
      (node (ref "U3") (pin "19") (pinfunction "HO_19") (pintype "passive"))
    )
    (net (code "45") (name "unconnected-(U3-SYNCOUT-Pad1)") (class "Default")
      (node (ref "U3") (pin "1") (pinfunction "SYNCOUT_1") (pintype "passive"))
    )
  )
)
